# YurtLightsOfLove.net
KiCad netlist of a schematic drawn in EAGLE
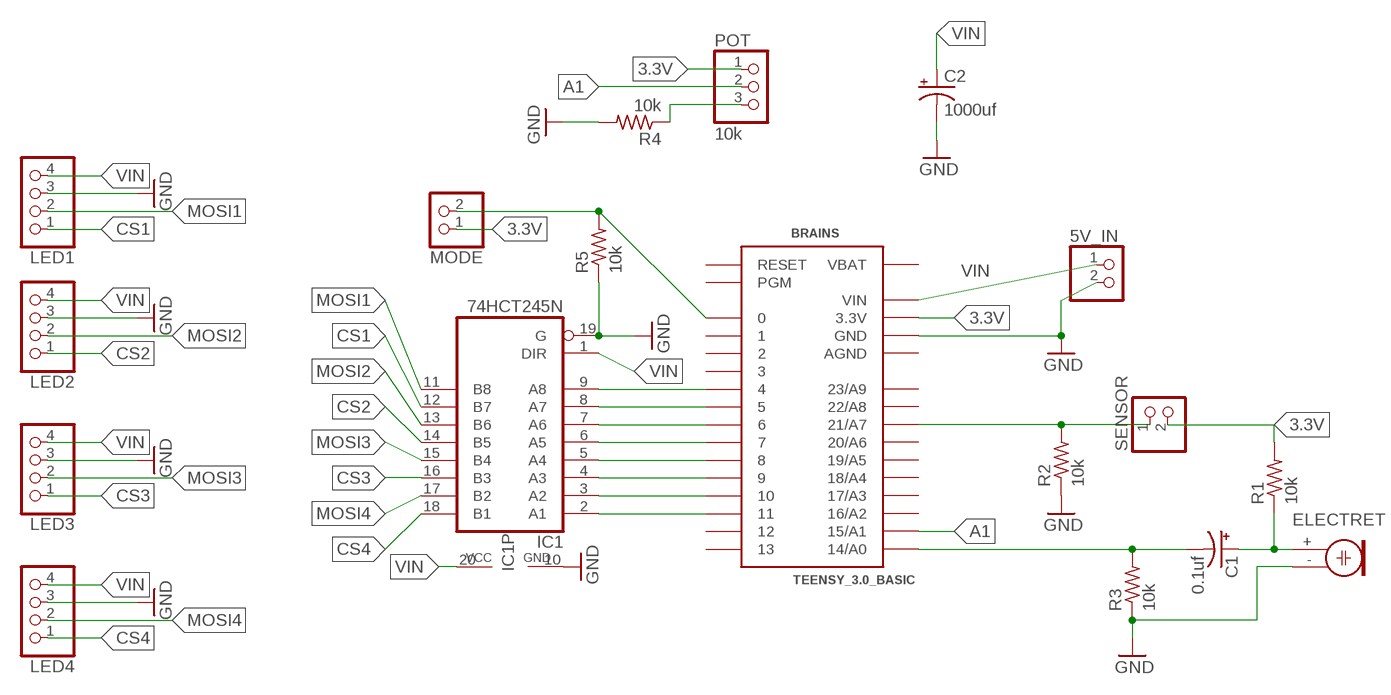
[diagram p0: schematic, sheet 1]

(export (version "E")
  (design (tool "Eeschema 10.0.6"))
  (components
    (comp (ref "5V_IN")
      (value "PINHD-1X2")
      (footprint "eagle-import:1X02")
      (fields (field (name "ADAFRUITPART") ".1\" screw terminal block"))
      (libsource (lib "eagle-import") (part "PINHD-1X2"))
    )
    (comp (ref "BRAINS")
      (value "TEENSY_3.0_BASIC")
      (footprint "eagle-import:TEENSY_3.0_BASIC")
      (libsource (lib "eagle-import") (part "TEENSY_3.0_BASIC"))
    )
    (comp (ref "C1")
      (value "0.1uf")
      (footprint "eagle-import:E5-5")
      (libsource (lib "eagle-import") (part "CPOL-USE5-5"))
    )
    (comp (ref "C2")
      (value "1000uf")
      (footprint "eagle-import:E3,5-8")
      (libsource (lib "eagle-import") (part "CPOL-USE3.5-8"))
    )
    (comp (ref "ELECTRET")
      (value "ELECTRET")
      (footprint "eagle-import:9.7ELECTRET")
      (libsource (lib "eagle-import") (part "ELECTRET"))
    )
    (comp (ref "IC1")
      (value "74HCT245N")
      (footprint "eagle-import:DIL20")
      (fields (field (name "OC_NEWARK") "unknown"))
      (libsource (lib "eagle-import") (part "74245NHCT"))
    )
    (comp (ref "LED1")
      (value "PINHD-1X4")
      (footprint "eagle-import:1X04")
      (libsource (lib "eagle-import") (part "PINHD-1X4"))
    )
    (comp (ref "LED2")
      (value "PINHD-1X4")
      (footprint "eagle-import:1X04")
      (libsource (lib "eagle-import") (part "PINHD-1X4"))
    )
    (comp (ref "LED3")
      (value "PINHD-1X4")
      (footprint "eagle-import:1X04")
      (libsource (lib "eagle-import") (part "PINHD-1X4"))
    )
    (comp (ref "LED4")
      (value "PINHD-1X4")
      (footprint "eagle-import:1X04")
      (libsource (lib "eagle-import") (part "PINHD-1X4"))
    )
    (comp (ref "MODE")
      (value "PINHD-1X2")
      (footprint "eagle-import:1X02")
      (fields (field (name "ADAFRUITPART") ".1\" screw terminal block"))
      (libsource (lib "eagle-import") (part "PINHD-1X2"))
    )
    (comp (ref "POT")
      (value "10k")
      (footprint "eagle-import:1X03")
      (fields (field (name "ADAFRUITPART") ".1\" screw terminal block"))
      (libsource (lib "eagle-import") (part "PINHD-1X3"))
    )
    (comp (ref "R1")
      (value "10k")
      (footprint "eagle-import:0207_10")
      (libsource (lib "eagle-import") (part "R-US_0207/10"))
    )
    (comp (ref "R2")
      (value "10k")
      (footprint "eagle-import:0207_10")
      (libsource (lib "eagle-import") (part "R-US_0207/10"))
    )
    (comp (ref "R3")
      (value "10k")
      (footprint "eagle-import:0207_10")
      (libsource (lib "eagle-import") (part "R-US_0207/10"))
    )
    (comp (ref "R4")
      (value "10k")
      (footprint "eagle-import:0207_10")
      (libsource (lib "eagle-import") (part "R-US_0207/10"))
    )
    (comp (ref "R5")
      (value "10k")
      (footprint "eagle-import:0207_10")
      (libsource (lib "eagle-import") (part "R-US_0207/10"))
    )
    (comp (ref "SENSOR")
      (value "PINHD-1X2")
      (footprint "eagle-import:1X02")
      (fields (field (name "ADAFRUITPART") ".1\" screw terminal block"))
      (libsource (lib "eagle-import") (part "PINHD-1X2"))
    )
  )
  (nets
    (net (code "1") (name "/AGND") (class "Default")
      (node (ref "BRAINS") (pin "AGND") (pinfunction "AGND_AGND") (pintype "power_in"))
    )
    (net (code "2") (name "/VBAT") (class "Default")
      (node (ref "BRAINS") (pin "VBAT") (pinfunction "VBAT_VBAT") (pintype "power_in"))
    )
    (net (code "3") (name "3.3V") (class "Default")
      (node (ref "BRAINS") (pin "3.3V") (pinfunction "3.3V_3.3V") (pintype "power_in"))
      (node (ref "BRAINS") (pin "3.3V1") (pinfunction "3.3V_3.3V1") (pintype "power_in"))
      (node (ref "MODE") (pin "1") (pinfunction "1_1") (pintype "passive"))
      (node (ref "POT") (pin "1") (pinfunction "1_1") (pintype "passive"))
      (node (ref "R1") (pin "2") (pinfunction "2_2") (pintype "passive"))
      (node (ref "SENSOR") (pin "2") (pinfunction "2_2") (pintype "passive"))
    )
    (net (code "4") (name "A1") (class "Default")
      (node (ref "BRAINS") (pin "15/A1") (pinfunction "15/A1_15/A1") (pintype "bidirectional"))
      (node (ref "POT") (pin "2") (pinfunction "2_2") (pintype "passive"))
    )
    (net (code "5") (name "CS1") (class "Default")
      (node (ref "IC1") (pin "12") (pinfunction "B7_12") (pintype "bidirectional"))
      (node (ref "LED1") (pin "1") (pinfunction "1_1") (pintype "passive"))
    )
    (net (code "6") (name "CS2") (class "Default")
      (node (ref "IC1") (pin "14") (pinfunction "B5_14") (pintype "bidirectional"))
      (node (ref "LED2") (pin "1") (pinfunction "1_1") (pintype "passive"))
    )
    (net (code "7") (name "CS3") (class "Default")
      (node (ref "IC1") (pin "16") (pinfunction "B3_16") (pintype "bidirectional"))
      (node (ref "LED3") (pin "1") (pinfunction "1_1") (pintype "passive"))
    )
    (net (code "8") (name "CS4") (class "Default")
      (node (ref "IC1") (pin "18") (pinfunction "B1_18") (pintype "bidirectional"))
      (node (ref "LED4") (pin "1") (pinfunction "1_1") (pintype "passive"))
    )
    (net (code "9") (name "GND") (class "Default")
      (node (ref "5V_IN") (pin "2") (pinfunction "2_2") (pintype "passive"))
      (node (ref "BRAINS") (pin "GND") (pinfunction "GND_GND") (pintype "power_in"))
      (node (ref "BRAINS") (pin "GND1") (pinfunction "GND_GND1") (pintype "power_in"))
      (node (ref "C2") (pin "-") (pinfunction "-_-") (pintype "passive"))
      (node (ref "ELECTRET") (pin "-") (pinfunction "1_-") (pintype "passive"))
      (node (ref "IC1") (pin "10") (pinfunction "GND_10") (pintype "power_in"))
      (node (ref "IC1") (pin "19") (pinfunction "G_19") (pintype "input"))
      (node (ref "LED1") (pin "3") (pinfunction "3_3") (pintype "passive"))
      (node (ref "LED2") (pin "3") (pinfunction "3_3") (pintype "passive"))
      (node (ref "LED3") (pin "3") (pinfunction "3_3") (pintype "passive"))
      (node (ref "LED4") (pin "3") (pinfunction "3_3") (pintype "passive"))
      (node (ref "R2") (pin "1") (pinfunction "1_1") (pintype "passive"))
      (node (ref "R3") (pin "1") (pinfunction "1_1") (pintype "passive"))
      (node (ref "R4") (pin "2") (pinfunction "2_2") (pintype "passive"))
      (node (ref "R5") (pin "1") (pinfunction "1_1") (pintype "passive"))
    )
    (net (code "10") (name "MOSI1") (class "Default")
      (node (ref "IC1") (pin "11") (pinfunction "B8_11") (pintype "bidirectional"))
      (node (ref "LED1") (pin "2") (pinfunction "2_2") (pintype "passive"))
    )
    (net (code "11") (name "MOSI2") (class "Default")
      (node (ref "IC1") (pin "13") (pinfunction "B6_13") (pintype "bidirectional"))
      (node (ref "LED2") (pin "2") (pinfunction "2_2") (pintype "passive"))
    )
    (net (code "12") (name "MOSI3") (class "Default")
      (node (ref "IC1") (pin "15") (pinfunction "B4_15") (pintype "bidirectional"))
      (node (ref "LED3") (pin "2") (pinfunction "2_2") (pintype "passive"))
    )
    (net (code "13") (name "MOSI4") (class "Default")
      (node (ref "IC1") (pin "17") (pinfunction "B2_17") (pintype "bidirectional"))
      (node (ref "LED4") (pin "2") (pinfunction "2_2") (pintype "passive"))
    )
    (net (code "14") (name "Net-(BRAINS-Pad0)") (class "Default")
      (node (ref "BRAINS") (pin "0") (pinfunction "0_0") (pintype "bidirectional"))
      (node (ref "MODE") (pin "2") (pinfunction "2_2") (pintype "passive"))
      (node (ref "R5") (pin "2") (pinfunction "2_2") (pintype "passive"))
    )
    (net (code "15") (name "Net-(BRAINS-Pad14{slash}A0)") (class "Default")
      (node (ref "BRAINS") (pin "14/A0") (pinfunction "14/A0_14/A0") (pintype "bidirectional"))
      (node (ref "C1") (pin "-") (pinfunction "-_-") (pintype "passive"))
      (node (ref "R3") (pin "2") (pinfunction "2_2") (pintype "passive"))
    )
    (net (code "16") (name "Net-(BRAINS-Pad21{slash}A7)") (class "Default")
      (node (ref "BRAINS") (pin "21/A7") (pinfunction "21/A7_21/A7") (pintype "bidirectional"))
      (node (ref "R2") (pin "2") (pinfunction "2_2") (pintype "passive"))
      (node (ref "SENSOR") (pin "1") (pinfunction "1_1") (pintype "passive"))
    )
    (net (code "17") (name "Net-(ELECTRET-2)") (class "Default")
      (node (ref "C1") (pin "+") (pinfunction "+_+") (pintype "passive"))
      (node (ref "ELECTRET") (pin "+") (pinfunction "2_+") (pintype "passive"))
      (node (ref "R1") (pin "1") (pinfunction "1_1") (pintype "passive"))
    )
    (net (code "18") (name "Net-(IC1A-A1)") (class "Default")
      (node (ref "BRAINS") (pin "11") (pinfunction "11_11") (pintype "bidirectional"))
      (node (ref "IC1") (pin "2") (pinfunction "A1_2") (pintype "bidirectional"))
    )
    (net (code "19") (name "Net-(IC1A-A2)") (class "Default")
      (node (ref "BRAINS") (pin "10") (pinfunction "10_10") (pintype "bidirectional"))
      (node (ref "IC1") (pin "3") (pinfunction "A2_3") (pintype "bidirectional"))
    )
    (net (code "20") (name "Net-(IC1A-A3)") (class "Default")
      (node (ref "BRAINS") (pin "9") (pinfunction "9_9") (pintype "bidirectional"))
      (node (ref "IC1") (pin "4") (pinfunction "A3_4") (pintype "bidirectional"))
    )
    (net (code "21") (name "Net-(IC1A-A4)") (class "Default")
      (node (ref "BRAINS") (pin "8") (pinfunction "8_8") (pintype "bidirectional"))
      (node (ref "IC1") (pin "5") (pinfunction "A4_5") (pintype "bidirectional"))
    )
    (net (code "22") (name "Net-(IC1A-A5)") (class "Default")
      (node (ref "BRAINS") (pin "7") (pinfunction "7_7") (pintype "bidirectional"))
      (node (ref "IC1") (pin "6") (pinfunction "A5_6") (pintype "bidirectional"))
    )
    (net (code "23") (name "Net-(IC1A-A6)") (class "Default")
      (node (ref "BRAINS") (pin "6") (pinfunction "6_6") (pintype "bidirectional"))
      (node (ref "IC1") (pin "7") (pinfunction "A6_7") (pintype "bidirectional"))
    )
    (net (code "24") (name "Net-(IC1A-A7)") (class "Default")
      (node (ref "BRAINS") (pin "5") (pinfunction "5_5") (pintype "bidirectional"))
      (node (ref "IC1") (pin "8") (pinfunction "A7_8") (pintype "bidirectional"))
    )
    (net (code "25") (name "Net-(IC1A-A8)") (class "Default")
      (node (ref "BRAINS") (pin "4") (pinfunction "4_4") (pintype "bidirectional"))
      (node (ref "IC1") (pin "9") (pinfunction "A8_9") (pintype "bidirectional"))
    )
    (net (code "26") (name "Net-(POT-Pad3)") (class "Default")
      (node (ref "POT") (pin "3") (pinfunction "3_3") (pintype "passive"))
      (node (ref "R4") (pin "1") (pinfunction "1_1") (pintype "passive"))
    )
    (net (code "27") (name "VIN") (class "Default")
      (node (ref "5V_IN") (pin "1") (pinfunction "1_1") (pintype "passive"))
      (node (ref "BRAINS") (pin "VIN") (pinfunction "VIN_VIN") (pintype "power_in"))
      (node (ref "C2") (pin "+") (pinfunction "+_+") (pintype "passive"))
      (node (ref "IC1") (pin "1") (pinfunction "DIR_1") (pintype "input"))
      (node (ref "IC1") (pin "20") (pinfunction "VCC_20") (pintype "power_in"))
      (node (ref "LED1") (pin "4") (pinfunction "4_4") (pintype "passive"))
      (node (ref "LED2") (pin "4") (pinfunction "4_4") (pintype "passive"))
      (node (ref "LED3") (pin "4") (pinfunction "4_4") (pintype "passive"))
      (node (ref "LED4") (pin "4") (pinfunction "4_4") (pintype "passive"))
    )
    (net (code "28") (name "unconnected-(BRAINS-Pad1)") (class "Default")
      (node (ref "BRAINS") (pin "1") (pinfunction "1_1") (pintype "bidirectional"))
    )
    (net (code "29") (name "unconnected-(BRAINS-Pad2)") (class "Default")
      (node (ref "BRAINS") (pin "2") (pinfunction "2_2") (pintype "bidirectional"))
    )
    (net (code "30") (name "unconnected-(BRAINS-Pad3)") (class "Default")
      (node (ref "BRAINS") (pin "3") (pinfunction "3_3") (pintype "bidirectional"))
    )
    (net (code "31") (name "unconnected-(BRAINS-Pad12)") (class "Default")
      (node (ref "BRAINS") (pin "12") (pinfunction "12_12") (pintype "bidirectional"))
    )
    (net (code "32") (name "unconnected-(BRAINS-Pad13)") (class "Default")
      (node (ref "BRAINS") (pin "13") (pinfunction "13_13") (pintype "bidirectional"))
    )
    (net (code "33") (name "unconnected-(BRAINS-Pad16{slash}A2)") (class "Default")
      (node (ref "BRAINS") (pin "16/A2") (pinfunction "16/A2_16/A2") (pintype "bidirectional"))
    )
    (net (code "34") (name "unconnected-(BRAINS-Pad17{slash}A3)") (class "Default")
      (node (ref "BRAINS") (pin "17/A3") (pinfunction "17/A3_17/A3") (pintype "bidirectional"))
    )
    (net (code "35") (name "unconnected-(BRAINS-Pad18{slash}A4)") (class "Default")
      (node (ref "BRAINS") (pin "18/A4") (pinfunction "18/A4_18/A4") (pintype "bidirectional"))
    )
    (net (code "36") (name "unconnected-(BRAINS-Pad19{slash}A5)") (class "Default")
      (node (ref "BRAINS") (pin "19/A5") (pinfunction "19/A5_19/A5") (pintype "bidirectional"))
    )
    (net (code "37") (name "unconnected-(BRAINS-Pad20{slash}A6)") (class "Default")
      (node (ref "BRAINS") (pin "20/A6") (pinfunction "20/A6_20/A6") (pintype "bidirectional"))
    )
    (net (code "38") (name "unconnected-(BRAINS-Pad22{slash}A8)") (class "Default")
      (node (ref "BRAINS") (pin "22/A8") (pinfunction "22/A8_22/A8") (pintype "bidirectional"))
    )
    (net (code "39") (name "unconnected-(BRAINS-Pad23{slash}A9)") (class "Default")
      (node (ref "BRAINS") (pin "23/A9") (pinfunction "23/A9_23/A9") (pintype "bidirectional"))
    )
    (net (code "40") (name "unconnected-(BRAINS-PadPGM)") (class "Default")
      (node (ref "BRAINS") (pin "PGM") (pinfunction "PGM_PGM") (pintype "bidirectional"))
    )
    (net (code "41") (name "unconnected-(BRAINS-PadRESET)") (class "Default")
      (node (ref "BRAINS") (pin "RESET") (pinfunction "RESET_RESET") (pintype "bidirectional"))
    )
  )
)
